# micro_schem.net
KiCad netlist of a schematic drawn in Altium Designer
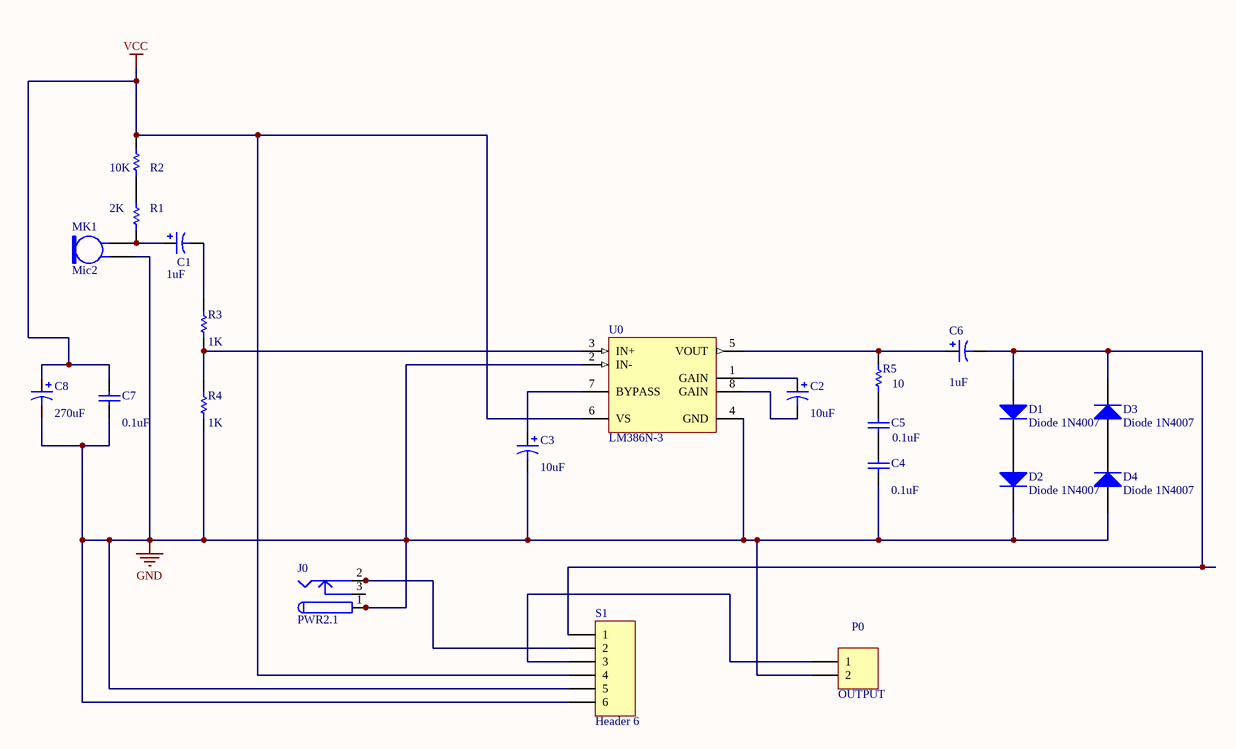
[diagram p0: micro_schem.SchDoc]

(export (version "E")
  (design (tool "Eeschema 10.0.6"))
  (components
    (comp (ref "C1")
      (value "1uF")
      (footprint "RB7.6-15")
      (description "Polarized Capacitor (Radial)")
      (fields (field (name "PUBLISHER") "Altium Limited"))
      (libsource (lib "Miscellaneous Devices") (part "Cap Pol1"))
    )
    (comp (ref "C2")
      (value "10uF")
      (footprint "RB7.6-15")
      (description "Polarized Capacitor (Radial)")
      (fields (field (name "PUBLISHER") "Altium Limited"))
      (libsource (lib "Miscellaneous Devices") (part "Cap Pol1"))
    )
    (comp (ref "C3")
      (value "10uF")
      (footprint "RB7.6-15")
      (description "Polarized Capacitor (Radial)")
      (fields (field (name "PUBLISHER") "Altium Limited"))
      (libsource (lib "Miscellaneous Devices") (part "Cap Pol1"))
    )
    (comp (ref "C4")
      (value "0.1uF")
      (footprint "RAD-0.3")
      (description "Capacitor")
      (fields (field (name "PUBLISHER") "Altium Limited"))
      (libsource (lib "Miscellaneous Devices") (part "Cap"))
    )
    (comp (ref "C5")
      (value "0.1uF")
      (footprint "RAD-0.3")
      (description "Capacitor")
      (fields (field (name "PUBLISHER") "Altium Limited"))
      (libsource (lib "Miscellaneous Devices") (part "Cap"))
    )
    (comp (ref "C6")
      (value "1uF")
      (footprint "RB7.6-15")
      (description "Polarized Capacitor (Radial)")
      (fields (field (name "PUBLISHER") "Altium Limited"))
      (libsource (lib "Miscellaneous Devices") (part "Cap Pol1"))
    )
    (comp (ref "C7")
      (value "0.1uF")
      (footprint "RAD-0.3")
      (description "Capacitor")
      (fields (field (name "PUBLISHER") "Altium Limited"))
      (libsource (lib "Miscellaneous Devices") (part "Cap"))
    )
    (comp (ref "C8")
      (value "270uF")
      (footprint "RB7.6-15")
      (description "Polarized Capacitor (Radial)")
      (fields (field (name "PUBLISHER") "Altium Limited"))
      (libsource (lib "Miscellaneous Devices") (part "Cap Pol1"))
    )
    (comp (ref "D1")
      (value "Diode 1N4007")
      (footprint "DIO10.46-5.3x2.8")
      (description "1 Amp General Purpose Rectifier")
      (fields (field (name "PUBLISHER") "Altium Limited"))
      (libsource (lib "Miscellaneous Devices") (part "Diode 1N4007"))
    )
    (comp (ref "D2")
      (value "Diode 1N4007")
      (footprint "DIO10.46-5.3x2.8")
      (description "1 Amp General Purpose Rectifier")
      (fields (field (name "PUBLISHER") "Altium Limited"))
      (libsource (lib "Miscellaneous Devices") (part "Diode 1N4007"))
    )
    (comp (ref "D3")
      (value "Diode 1N4007")
      (footprint "DIO10.46-5.3x2.8")
      (description "1 Amp General Purpose Rectifier")
      (fields (field (name "PUBLISHER") "Altium Limited"))
      (libsource (lib "Miscellaneous Devices") (part "Diode 1N4007"))
    )
    (comp (ref "D4")
      (value "Diode 1N4007")
      (footprint "DIO10.46-5.3x2.8")
      (description "1 Amp General Purpose Rectifier")
      (fields (field (name "PUBLISHER") "Altium Limited"))
      (libsource (lib "Miscellaneous Devices") (part "Diode 1N4007"))
    )
    (comp (ref "J0")
      (value "PWR2.1")
      (footprint "PcbLib1:KLD-0202")
      (description "Low Voltage Power Supply Connector")
      (fields (field (name "PUBLISHER") "Altium Limited"))
      (libsource (lib "Miscellaneous Connectors") (part "PWR2.5"))
    )
    (comp (ref "MK1")
      (value "Mic2")
      (footprint "PIN2")
      (description "Microphone")
      (fields (field (name "PUBLISHER") "Altium Limited"))
      (libsource (lib "Miscellaneous Devices") (part "Mic2"))
    )
    (comp (ref "P0")
      (value "OUTPUT")
      (footprint "HDR1X2")
      (description "Header, 2-Pin")
      (fields (field (name "PUBLISHER") "Altium Limited"))
      (libsource (lib "Miscellaneous Connectors") (part "Header 2"))
    )
    (comp (ref "R1")
      (value "2K")
      (footprint "AXIAL-0.3")
      (description "Resistor")
      (fields (field (name "PUBLISHER") "Altium Limited"))
      (libsource (lib "Miscellaneous Devices") (part "Res1"))
    )
    (comp (ref "R2")
      (value "10K")
      (footprint "AXIAL-0.3")
      (description "Resistor")
      (fields (field (name "PUBLISHER") "Altium Limited"))
      (libsource (lib "Miscellaneous Devices") (part "Res1"))
    )
    (comp (ref "R3")
      (value "1K")
      (footprint "AXIAL-0.3")
      (description "Resistor")
      (fields (field (name "PUBLISHER") "Altium Limited"))
      (libsource (lib "Miscellaneous Devices") (part "Res1"))
    )
    (comp (ref "R4")
      (value "1K")
      (footprint "AXIAL-0.3")
      (description "Resistor")
      (fields (field (name "PUBLISHER") "Altium Limited"))
      (libsource (lib "Miscellaneous Devices") (part "Res1"))
    )
    (comp (ref "R5")
      (value "10")
      (footprint "AXIAL-0.3")
      (description "Resistor")
      (fields (field (name "PUBLISHER") "Altium Limited"))
      (libsource (lib "Miscellaneous Devices") (part "Res1"))
    )
    (comp (ref "S1")
      (value "Header 6")
      (footprint "HDR1X6")
      (description "Header, 6-Pin")
      (fields (field (name "PUBLISHER") "Altium Limited"))
      (libsource (lib "Miscellaneous Connectors") (part "Header 6"))
    )
    (comp (ref "U0")
      (value "LM386N-3")
      (footprint "N08E")
      (description "Low Voltage Audio Power Amplifier, 8-pin MDIP")
      (fields
        (field (name "MANUFACTURER") "National Semiconductor")
        (field (name "PUBLISHER") "Altium Limited")
      )
      (libsource (lib "NSC Audio") (part "LM386N-3"))
    )
  )
  (nets
    (net (code "1") (name "GND") (class "Default")
      (node (ref "C3") (pin "2") (pinfunction "2_2") (pintype "passive"))
      (node (ref "C4") (pin "1") (pinfunction "1_1") (pintype "passive"))
      (node (ref "C7") (pin "1") (pinfunction "1_1") (pintype "passive"))
      (node (ref "C8") (pin "2") (pinfunction "2_2") (pintype "passive"))
      (node (ref "D2") (pin "2") (pinfunction "K_2") (pintype "passive"))
      (node (ref "D4") (pin "1") (pinfunction "A_1") (pintype "passive"))
      (node (ref "J0") (pin "1") (pinfunction "1_1") (pintype "power_in"))
      (node (ref "J0") (pin "1A") (pinfunction "1A_1A") (pintype "power_in"))
      (node (ref "MK1") (pin "1") (pinfunction "1_1") (pintype "passive"))
      (node (ref "P0") (pin "2") (pinfunction "2_2") (pintype "passive"))
      (node (ref "R4") (pin "1") (pinfunction "1_1") (pintype "passive"))
      (node (ref "S1") (pin "5") (pinfunction "5_5") (pintype "passive"))
      (node (ref "S1") (pin "6") (pinfunction "6_6") (pintype "passive"))
      (node (ref "U0") (pin "2") (pinfunction "IN-_2") (pintype "input"))
      (node (ref "U0") (pin "4") (pinfunction "GND_4") (pintype "power_in"))
    )
    (net (code "2") (name "Net-(C1-Pad1)") (class "Default")
      (node (ref "C1") (pin "1") (pinfunction "1_1") (pintype "passive"))
      (node (ref "MK1") (pin "2") (pinfunction "2_2") (pintype "passive"))
      (node (ref "R1") (pin "1") (pinfunction "1_1") (pintype "passive"))
    )
    (net (code "3") (name "Net-(C1-Pad2)") (class "Default")
      (node (ref "C1") (pin "2") (pinfunction "2_2") (pintype "passive"))
      (node (ref "R3") (pin "2") (pinfunction "2_2") (pintype "passive"))
    )
    (net (code "4") (name "Net-(C2-Pad1)") (class "Default")
      (node (ref "C2") (pin "1") (pinfunction "1_1") (pintype "passive"))
      (node (ref "U0") (pin "1") (pinfunction "GAIN_1") (pintype "passive"))
    )
    (net (code "5") (name "Net-(C2-Pad2)") (class "Default")
      (node (ref "C2") (pin "2") (pinfunction "2_2") (pintype "passive"))
      (node (ref "U0") (pin "8") (pinfunction "GAIN_8") (pintype "passive"))
    )
    (net (code "6") (name "Net-(C4-Pad2)") (class "Default")
      (node (ref "C4") (pin "2") (pinfunction "2_2") (pintype "passive"))
      (node (ref "C5") (pin "1") (pinfunction "1_1") (pintype "passive"))
    )
    (net (code "7") (name "Net-(C5-Pad2)") (class "Default")
      (node (ref "C5") (pin "2") (pinfunction "2_2") (pintype "passive"))
      (node (ref "R5") (pin "1") (pinfunction "1_1") (pintype "passive"))
    )
    (net (code "8") (name "Net-(D1-A)") (class "Default")
      (node (ref "C6") (pin "2") (pinfunction "2_2") (pintype "passive"))
      (node (ref "D1") (pin "1") (pinfunction "A_1") (pintype "passive"))
      (node (ref "D3") (pin "2") (pinfunction "K_2") (pintype "passive"))
      (node (ref "S1") (pin "1") (pinfunction "1_1") (pintype "passive"))
    )
    (net (code "9") (name "Net-(D1-K)") (class "Default")
      (node (ref "D1") (pin "2") (pinfunction "K_2") (pintype "passive"))
      (node (ref "D2") (pin "1") (pinfunction "A_1") (pintype "passive"))
    )
    (net (code "10") (name "Net-(D3-A)") (class "Default")
      (node (ref "D3") (pin "1") (pinfunction "A_1") (pintype "passive"))
      (node (ref "D4") (pin "2") (pinfunction "K_2") (pintype "passive"))
    )
    (net (code "11") (name "Net-(J0-Pad2)") (class "Default")
      (node (ref "J0") (pin "2") (pinfunction "2_2") (pintype "power_in"))
      (node (ref "J0") (pin "2A") (pinfunction "2A_2A") (pintype "power_in"))
      (node (ref "S1") (pin "2") (pinfunction "2_2") (pintype "passive"))
    )
    (net (code "12") (name "Net-(J0-Pad3)") (class "Default")
      (node (ref "J0") (pin "3") (pinfunction "3_3") (pintype "power_in"))
      (node (ref "J0") (pin "3A") (pinfunction "3A_3A") (pintype "power_in"))
    )
    (net (code "13") (name "Net-(P0-Pad1)") (class "Default")
      (node (ref "P0") (pin "1") (pinfunction "1_1") (pintype "passive"))
      (node (ref "S1") (pin "3") (pinfunction "3_3") (pintype "passive"))
    )
    (net (code "14") (name "Net-(R1-Pad2)") (class "Default")
      (node (ref "R1") (pin "2") (pinfunction "2_2") (pintype "passive"))
      (node (ref "R2") (pin "1") (pinfunction "1_1") (pintype "passive"))
    )
    (net (code "15") (name "Net-(U0-BYPASS)") (class "Default")
      (node (ref "C3") (pin "1") (pinfunction "1_1") (pintype "passive"))
      (node (ref "U0") (pin "7") (pinfunction "BYPASS_7") (pintype "passive"))
    )
    (net (code "16") (name "Net-(U0-IN+)") (class "Default")
      (node (ref "R3") (pin "1") (pinfunction "1_1") (pintype "passive"))
      (node (ref "R4") (pin "2") (pinfunction "2_2") (pintype "passive"))
      (node (ref "U0") (pin "3") (pinfunction "IN+_3") (pintype "input"))
    )
    (net (code "17") (name "Net-(U0-VOUT)") (class "Default")
      (node (ref "C6") (pin "1") (pinfunction "1_1") (pintype "passive"))
      (node (ref "R5") (pin "2") (pinfunction "2_2") (pintype "passive"))
      (node (ref "U0") (pin "5") (pinfunction "VOUT_5") (pintype "output"))
    )
    (net (code "18") (name "VCC") (class "Default")
      (node (ref "C7") (pin "2") (pinfunction "2_2") (pintype "passive"))
      (node (ref "C8") (pin "1") (pinfunction "1_1") (pintype "passive"))
      (node (ref "R2") (pin "2") (pinfunction "2_2") (pintype "passive"))
      (node (ref "S1") (pin "4") (pinfunction "4_4") (pintype "passive"))
      (node (ref "U0") (pin "6") (pinfunction "VS_6") (pintype "power_in"))
    )
  )
)
